# ATTinyServo_v11.net
KiCad netlist of a schematic drawn in EAGLE
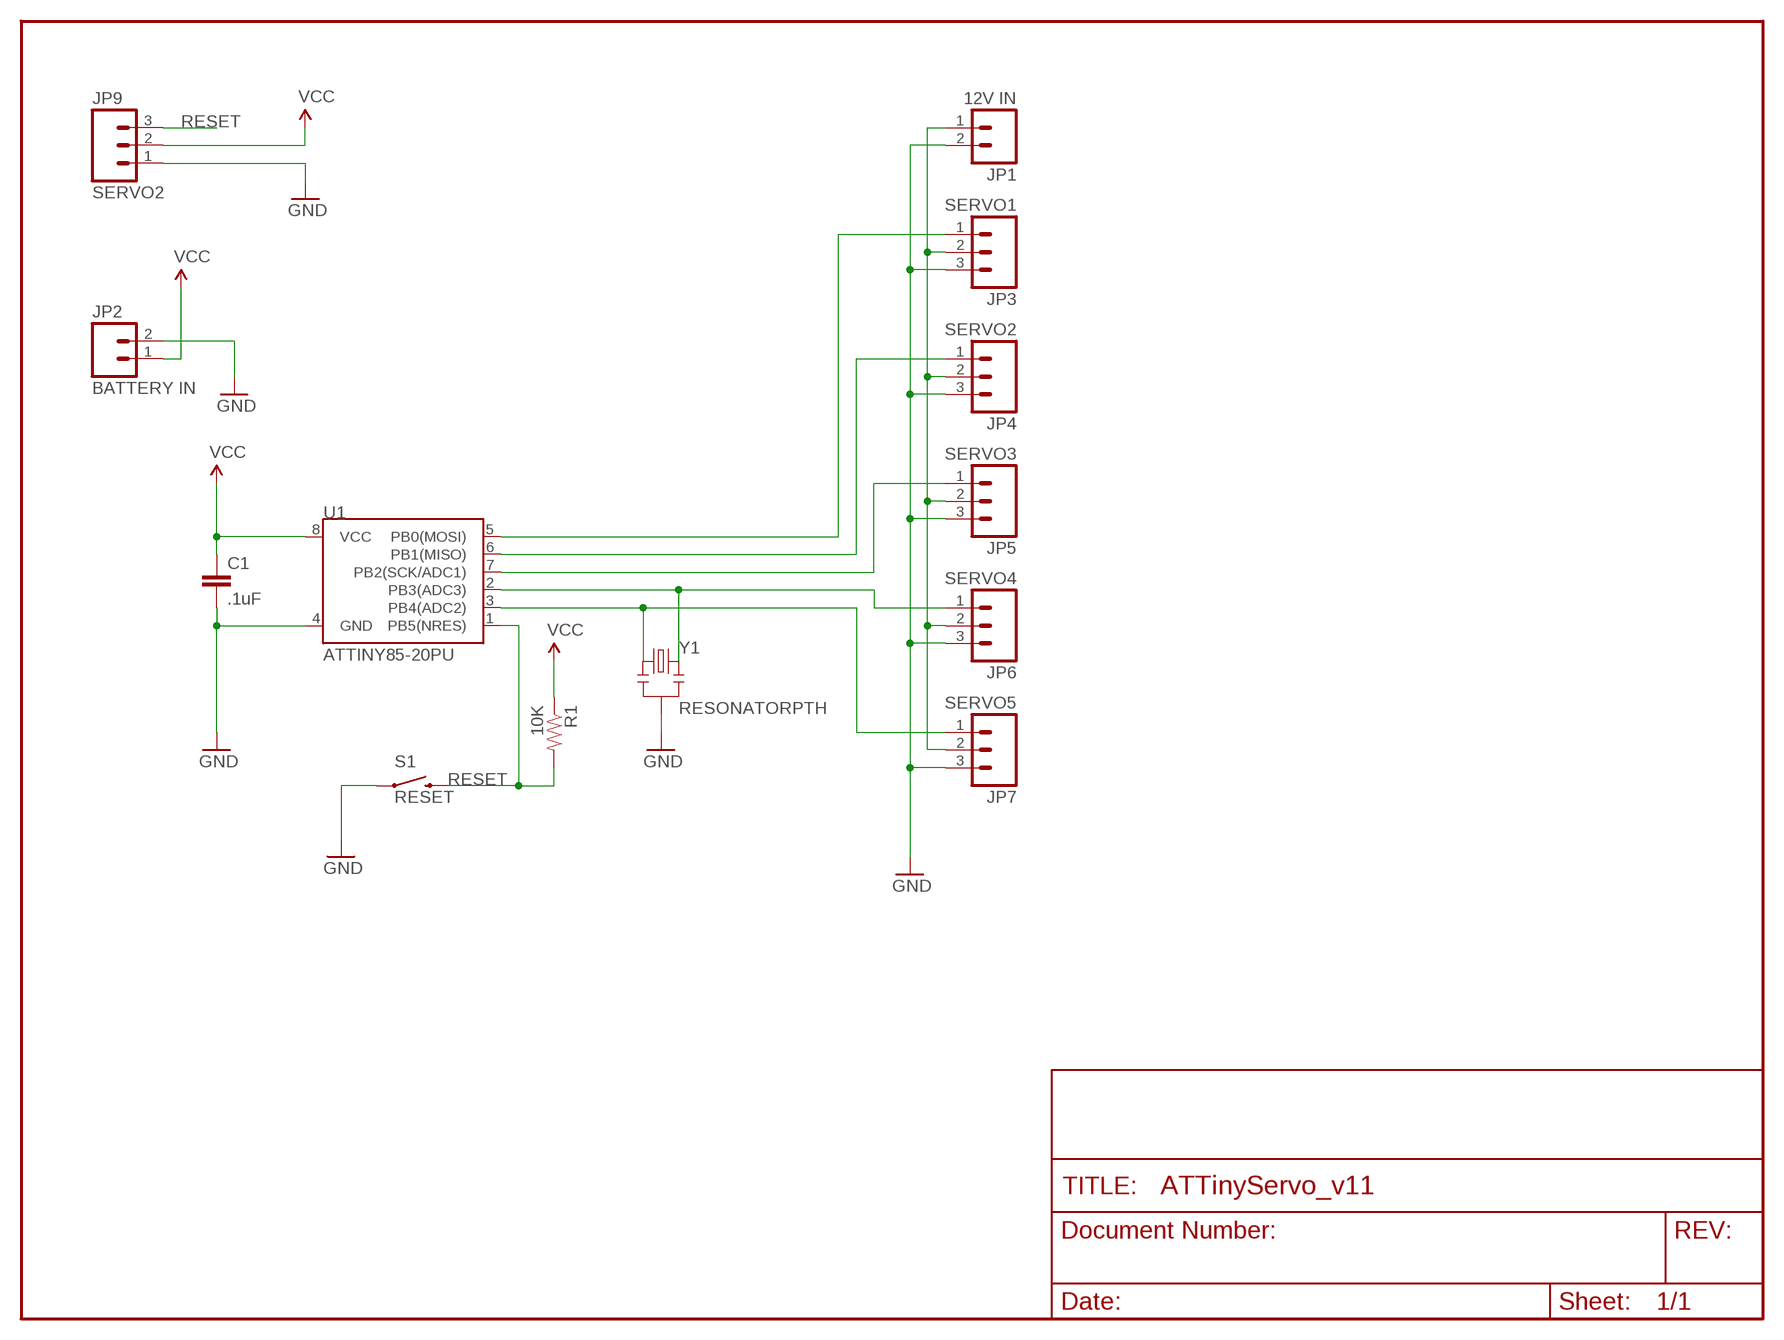
[diagram p0: schematic, sheet 1]

(export (version "E")
  (design (tool "Eeschema 10.0.6"))
  (components
    (comp (ref "C1")
      (value ".1uF")
      (footprint "eagle-import:CAP-PTH-SMALL-KIT")
      (libsource (lib "eagle-import") (part "CAPKIT"))
    )
    (comp (ref "JP1")
      (value "12V IN")
      (footprint "eagle-import:SCREWTERMINAL-3.5MM-2")
      (libsource (lib "eagle-import") (part "M023.5MM"))
    )
    (comp (ref "JP2")
      (value "BATTERY IN")
      (footprint "eagle-import:SCREWTERMINAL-3.5MM-2")
      (libsource (lib "eagle-import") (part "M023.5MM"))
    )
    (comp (ref "JP3")
      (value "SERVO1")
      (footprint "eagle-import:1X03")
      (libsource (lib "eagle-import") (part "M03PTH"))
    )
    (comp (ref "JP4")
      (value "SERVO2")
      (footprint "eagle-import:1X03")
      (libsource (lib "eagle-import") (part "M03PTH"))
    )
    (comp (ref "JP5")
      (value "SERVO3")
      (footprint "eagle-import:1X03")
      (libsource (lib "eagle-import") (part "M03PTH"))
    )
    (comp (ref "JP6")
      (value "SERVO4")
      (footprint "eagle-import:1X03")
      (libsource (lib "eagle-import") (part "M03PTH"))
    )
    (comp (ref "JP7")
      (value "SERVO5")
      (footprint "eagle-import:1X03")
      (libsource (lib "eagle-import") (part "M03PTH"))
    )
    (comp (ref "JP9")
      (value "SERVO2")
      (footprint "eagle-import:1X03")
      (libsource (lib "eagle-import") (part "M03PTH"))
    )
    (comp (ref "R1")
      (value "10K")
      (footprint "eagle-import:AXIAL-0.4")
      (libsource (lib "eagle-import") (part "RESISTORPTH-1/4W"))
    )
    (comp (ref "S1")
      (value "RESET")
      (footprint "eagle-import:TACTILE-PTH")
      (libsource (lib "eagle-import") (part "SWITCH-MOMENTARY-2PTH"))
    )
    (comp (ref "U1")
      (value "ATTINY85-20PU")
      (footprint "eagle-import:DIP08")
      (libsource (lib "eagle-import") (part "ATTINY45DIP8"))
    )
    (comp (ref "Y1")
      (value "RESONATORPTH")
      (footprint "eagle-import:RESONATOR-PTH")
      (libsource (lib "eagle-import") (part "RESONATORPTH"))
    )
  )
  (nets
    (net (code "1") (name "/RESET") (class "Default")
      (node (ref "JP9") (pin "3") (pinfunction "3_3") (pintype "passive"))
      (node (ref "R1") (pin "P$2") (pinfunction "2_P$2") (pintype "passive"))
      (node (ref "S1") (pin "3") (pinfunction "2_3") (pintype "passive"))
      (node (ref "U1") (pin "1") (pinfunction "PB5(NRES)_1") (pintype "bidirectional"))
    )
    (net (code "2") (name "GND") (class "Default")
      (node (ref "C1") (pin "2") (pinfunction "2_2") (pintype "passive"))
      (node (ref "JP1") (pin "2") (pinfunction "2_2") (pintype "passive"))
      (node (ref "JP2") (pin "2") (pinfunction "2_2") (pintype "passive"))
      (node (ref "JP3") (pin "3") (pinfunction "3_3") (pintype "passive"))
      (node (ref "JP4") (pin "3") (pinfunction "3_3") (pintype "passive"))
      (node (ref "JP5") (pin "3") (pinfunction "3_3") (pintype "passive"))
      (node (ref "JP6") (pin "3") (pinfunction "3_3") (pintype "passive"))
      (node (ref "JP7") (pin "3") (pinfunction "3_3") (pintype "passive"))
      (node (ref "JP9") (pin "1") (pinfunction "1_1") (pintype "passive"))
      (node (ref "S1") (pin "1") (pinfunction "1_1") (pintype "passive"))
      (node (ref "U1") (pin "4") (pinfunction "GND_4") (pintype "bidirectional"))
      (node (ref "Y1") (pin "2") (pinfunction "2_2") (pintype "passive"))
    )
    (net (code "3") (name "Net-(JP1-Pad1)") (class "Default")
      (node (ref "JP1") (pin "1") (pinfunction "1_1") (pintype "passive"))
      (node (ref "JP3") (pin "2") (pinfunction "2_2") (pintype "passive"))
      (node (ref "JP4") (pin "2") (pinfunction "2_2") (pintype "passive"))
      (node (ref "JP5") (pin "2") (pinfunction "2_2") (pintype "passive"))
      (node (ref "JP6") (pin "2") (pinfunction "2_2") (pintype "passive"))
      (node (ref "JP7") (pin "2") (pinfunction "2_2") (pintype "passive"))
    )
    (net (code "4") (name "Net-(U1-PB0(MOSI))") (class "Default")
      (node (ref "JP3") (pin "1") (pinfunction "1_1") (pintype "passive"))
      (node (ref "U1") (pin "5") (pinfunction "PB0(MOSI)_5") (pintype "bidirectional"))
    )
    (net (code "5") (name "Net-(U1-PB1(MISO))") (class "Default")
      (node (ref "JP4") (pin "1") (pinfunction "1_1") (pintype "passive"))
      (node (ref "U1") (pin "6") (pinfunction "PB1(MISO)_6") (pintype "bidirectional"))
    )
    (net (code "6") (name "Net-(U1-PB2(SCK{slash}ADC1))") (class "Default")
      (node (ref "JP5") (pin "1") (pinfunction "1_1") (pintype "passive"))
      (node (ref "U1") (pin "7") (pinfunction "PB2(SCK/ADC1)_7") (pintype "bidirectional"))
    )
    (net (code "7") (name "Net-(U1-PB3(ADC3))") (class "Default")
      (node (ref "JP6") (pin "1") (pinfunction "1_1") (pintype "passive"))
      (node (ref "U1") (pin "2") (pinfunction "PB3(ADC3)_2") (pintype "bidirectional"))
      (node (ref "Y1") (pin "3") (pinfunction "3_3") (pintype "passive"))
    )
    (net (code "8") (name "Net-(U1-PB4(ADC2))") (class "Default")
      (node (ref "JP7") (pin "1") (pinfunction "1_1") (pintype "passive"))
      (node (ref "U1") (pin "3") (pinfunction "PB4(ADC2)_3") (pintype "bidirectional"))
      (node (ref "Y1") (pin "1") (pinfunction "1_1") (pintype "passive"))
    )
    (net (code "9") (name "VCC") (class "Default")
      (node (ref "C1") (pin "1") (pinfunction "1_1") (pintype "passive"))
      (node (ref "JP2") (pin "1") (pinfunction "1_1") (pintype "passive"))
      (node (ref "JP9") (pin "2") (pinfunction "2_2") (pintype "passive"))
      (node (ref "R1") (pin "P$1") (pinfunction "1_P$1") (pintype "passive"))
      (node (ref "U1") (pin "8") (pinfunction "VCC_8") (pintype "bidirectional"))
    )
  )
)
